# SDR_wt_Schema.net
KiCad netlist of a schematic drawn in Altium Designer
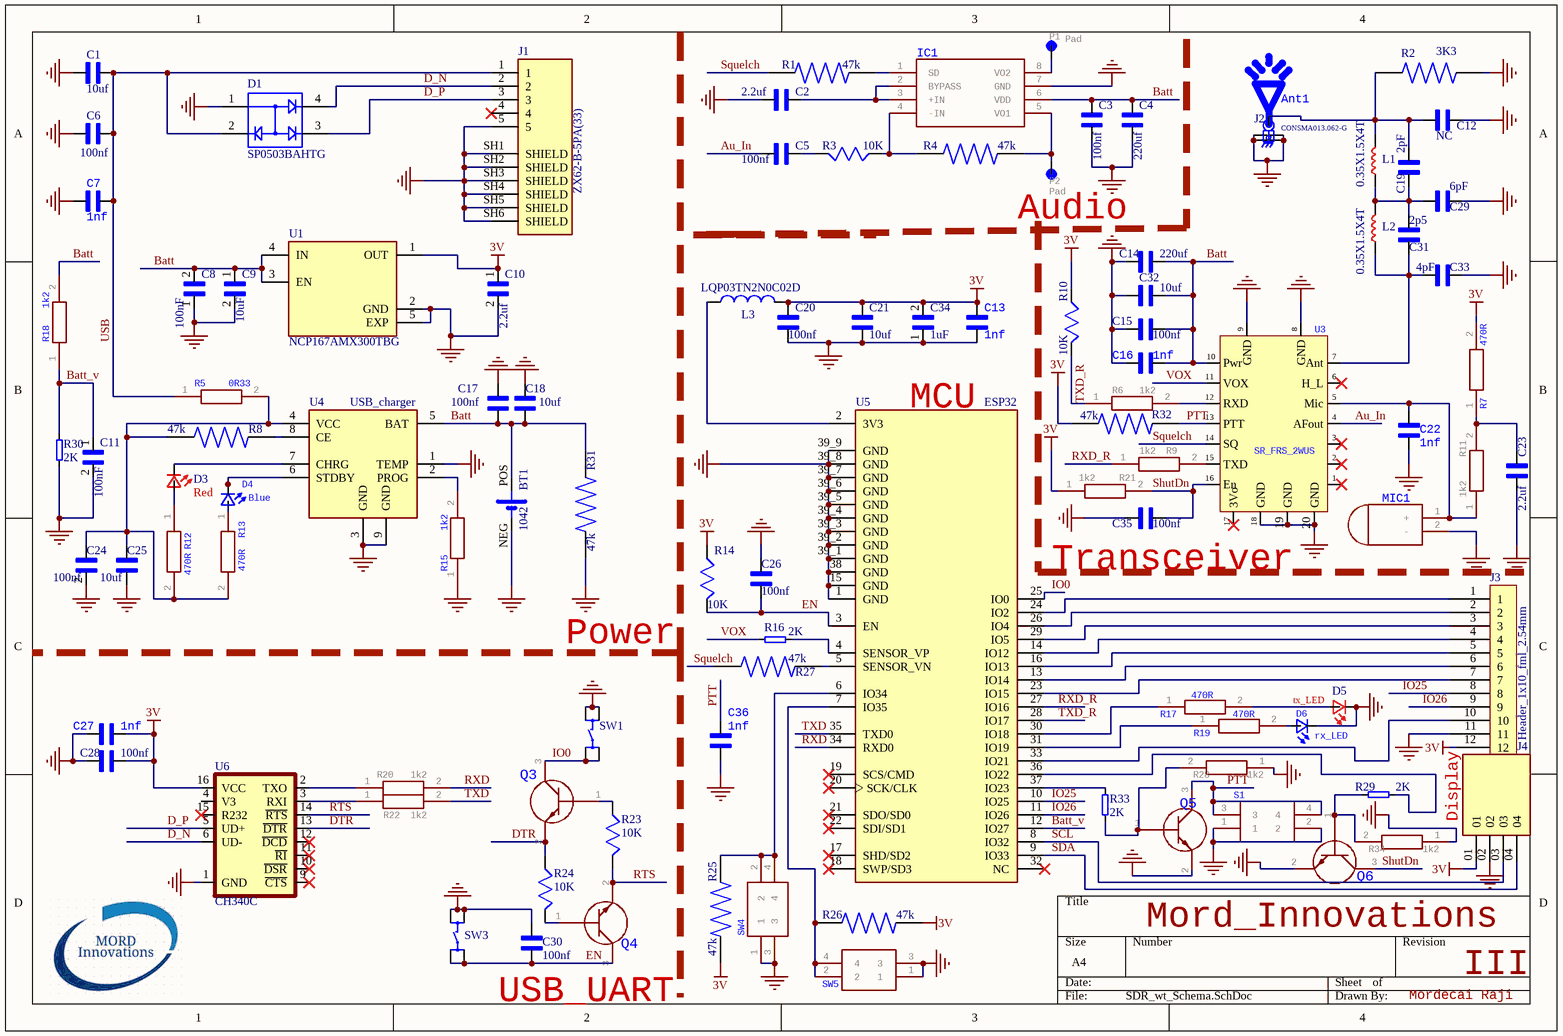
[diagram p0: SDR_wt_Schema.SchDoc]

(export (version "E")
  (design (tool "Eeschema 10.0.6"))
  (components
    (comp (ref "Ant1")
      (value "UHF_Antenna")
      (footprint "Antenna")
      (libsource (lib "SDR_wt_SchLib") (part "Antenna"))
    )
    (comp (ref "BT1")
      (value "1042")
      (footprint "BAT_1042")
      (fields (field (name "MF") "Laird Technologies"))
      (libsource (lib "SDR_wt_SchLib") (part "1042"))
    )
    (comp (ref "C1")
      (value "10uf")
      (footprint "CAPC1608X90N")
      (description "10ÂµF Â±10% 10V Ceramic Capacitor X5R 0603 _1608 Metric_")
      (fields (field (name "MP") "CL10A106KP8NNNC") (field (name "MF") "Samsung"))
      (libsource (lib "") (part "10uf_1"))
    )
    (comp (ref "C2")
      (value "2.2uf")
      (footprint "2u2 cap 0805")
      (description "SMT 0805 ceramic cap X7R 10V 2.2uF")
      (fields (field (name "MP") "GRM21BR71A225KA01L"))
      (libsource (lib "") (part "GRM21BR71A225KA01L_1"))
    )
    (comp (ref "C3")
      (value "100nf")
      (footprint "CAPC1005X55N")
      (description "0.1ÂµF Â±10% 16V Ceramic Capacitor X7R 0402 _1005 Metric_")
      (fields (field (name "MP") "CL05B104KO5NNNC") (field (name "MF") "Samsung Electro-Mechanics"))
      (libsource (lib "") (part "100nf_4"))
    )
    (comp (ref "C4")
      (value "220uf")
      (footprint "220uf_3v3")
      (description "GRM31CR60J227ME11L")
      (fields (field (name "DIGI-KEY_PART_NUMBER") "490-13970-1-ND") (field (name "MF") "Murata Electronics"))
      (libsource (lib "") (part "220uf_6v3_1"))
    )
    (comp (ref "C5")
      (value "100nf")
      (footprint "CAPC1005X55N")
      (description "0.1ÂµF Â±10% 16V Ceramic Capacitor X7R 0402 _1005 Metric_")
      (fields (field (name "MP") "CL05B104KO5NNNC") (field (name "MF") "Samsung Electro-Mechanics"))
      (libsource (lib "") (part "100nf_1"))
    )
    (comp (ref "C6")
      (value "100nf")
      (footprint "CAPC1005X55N")
      (description "0.1ÂµF Â±10% 16V Ceramic Capacitor X7R 0402 _1005 Metric_")
      (fields (field (name "MP") "CL05B104KO5NNNC") (field (name "MF") "Samsung Electro-Mechanics"))
      (libsource (lib "") (part "100nf_1"))
    )
    (comp (ref "C7") (value "1nf") (footprint "1nF CAP") (libsource (lib "") (part "1nF CAP_2")))
    (comp (ref "C8")
      (value "100nF")
      (footprint "CAPC1005X55N")
      (description "0.1ÂµF Â±10% 16V Ceramic Capacitor X7R 0402 _1005 Metric_")
      (fields (field (name "MP") "CL05B104KO5NNNC") (field (name "MF") "Samsung Electro-Mechanics"))
      (libsource (lib "") (part "100nf_2"))
    )
    (comp (ref "C9")
      (value "10uF")
      (footprint "CAPC1608X90N")
      (description "10ÂµF Â±10% 10V Ceramic Capacitor X5R 0603 _1608 Metric_")
      (fields (field (name "MP") "CL10A106KP8NNNC") (field (name "MF") "Samsung"))
      (libsource (lib "") (part "10uf_3"))
    )
    (comp (ref "C10")
      (value "2.2uf")
      (footprint "2u2 cap 0805")
      (description "SMT 0805 ceramic cap X7R 10V 2.2uF")
      (fields (field (name "MP") "GRM21BR71A225KA01L"))
      (libsource (lib "SDR_wt_SchLib") (part "GRM21BR71A225KA01L"))
    )
    (comp (ref "C11")
      (value "100nF")
      (footprint "CAPC1005X55N")
      (description "0.1ÂµF Â±10% 16V Ceramic Capacitor X7R 0402 _1005 Metric_")
      (fields (field (name "MP") "CL05B104KO5NNNC") (field (name "MF") "Samsung Electro-Mechanics"))
      (libsource (lib "SDR_wt_SchLib") (part "100nf"))
    )
    (comp (ref "C12")
      (value "NC")
      (footprint "CAPC1608X90N")
      (description "SMD Capacitor C0G(EIA) with Capacitance: 2.0pF Tol. 0.1pF. Rated Voltage: 100Vdc")
      (fields (field (name "MP") "GCM1885C2A2R0BA16D"))
      (libsource (lib "") (part "GCM1885C2A2R0BA16D_1"))
    )
    (comp (ref "C13") (value "1nf") (footprint "1nF CAP") (libsource (lib "") (part "1nF CAP_1")))
    (comp (ref "C14")
      (value "220uf")
      (footprint "220uf_3v3")
      (description "GRM31CR60J227ME11L")
      (fields (field (name "DIGI-KEY_PART_NUMBER") "490-13970-1-ND") (field (name "MF") "Murata Electronics"))
      (libsource (lib "SDR_wt_SchLib") (part "220uf_6v3"))
    )
    (comp (ref "C15")
      (value "100nf")
      (footprint "CAPC1005X55N")
      (description "0.1ÂµF Â±10% 16V Ceramic Capacitor X7R 0402 _1005 Metric_")
      (fields (field (name "MP") "CL05B104KO5NNNC") (field (name "MF") "Samsung Electro-Mechanics"))
      (libsource (lib "") (part "100nf_1"))
    )
    (comp (ref "C16") (value "1nf") (footprint "1nF CAP") (libsource (lib "SDR_wt_SchLib") (part "1nF CAP")))
    (comp (ref "C17")
      (value "100nf")
      (footprint "CAPC1005X55N")
      (description "0.1ÂµF Â±10% 16V Ceramic Capacitor X7R 0402 _1005 Metric_")
      (fields (field (name "MP") "CL05B104KO5NNNC") (field (name "MF") "Samsung Electro-Mechanics"))
      (libsource (lib "PowerCastle") (part "100nf"))
    )
    (comp (ref "C18")
      (value "10uf")
      (footprint "CAPC1608X90N")
      (description "10ÂµF Â±10% 10V Ceramic Capacitor X5R 0603 _1608 Metric_")
      (fields (field (name "MP") "CL10A106KP8NNNC") (field (name "MF") "Samsung"))
      (libsource (lib "") (part "10uf_2"))
    )
    (comp (ref "C19")
      (value "2pF")
      (footprint "CAPC1608X90N")
      (description "SMD Capacitor C0G(EIA) with Capacitance: 2.0pF Tol. 0.1pF. Rated Voltage: 100Vdc")
      (fields (field (name "MP") "GCM1885C2A2R0BA16D"))
      (libsource (lib "GCM1885C2A2R0BA16D") (part "GCM1885C2A2R0BA16D"))
    )
    (comp (ref "C20")
      (value "100nf")
      (footprint "CAPC1005X55N")
      (description "0.1ÂµF Â±10% 16V Ceramic Capacitor X7R 0402 _1005 Metric_")
      (fields (field (name "MP") "CL05B104KO5NNNC") (field (name "MF") "Samsung Electro-Mechanics"))
      (libsource (lib "PowerCastle") (part "100nf"))
    )
    (comp (ref "C21")
      (value "10uf")
      (footprint "CAPC1608X90N")
      (description "10ÂµF Â±10% 10V Ceramic Capacitor X5R 0603 _1608 Metric_")
      (fields (field (name "MP") "CL10A106KP8NNNC") (field (name "MF") "Samsung"))
      (libsource (lib "") (part "10uf_2"))
    )
    (comp (ref "C22") (value "1nf") (footprint "1nF CAP") (libsource (lib "") (part "1nF CAP_1")))
    (comp (ref "C23")
      (value "2.2uf")
      (footprint "2u2 cap 0805")
      (description "SMT 0805 ceramic cap X7R 10V 2.2uF")
      (fields (field (name "MP") "GRM21BR71A225KA01L"))
      (libsource (lib "") (part "GRM21BR71A225KA01L_2"))
    )
    (comp (ref "C24")
      (value "100nf")
      (footprint "CAPC1005X55N")
      (description "0.1ÂµF Â±10% 16V Ceramic Capacitor X7R 0402 _1005 Metric_")
      (fields (field (name "MP") "CL05B104KO5NNNC") (field (name "MF") "Samsung Electro-Mechanics"))
      (libsource (lib "") (part "100nf_3"))
    )
    (comp (ref "C25")
      (value "10uf")
      (footprint "CAPC1608X90N")
      (description "10ÂµF Â±10% 10V Ceramic Capacitor X5R 0603 _1608 Metric_")
      (fields (field (name "MP") "CL10A106KP8NNNC") (field (name "MF") "Samsung"))
      (libsource (lib "") (part "10uf_2"))
    )
    (comp (ref "C26")
      (value "100nf")
      (footprint "CAPC1005X55N")
      (description "0.1ÂµF Â±10% 16V Ceramic Capacitor X7R 0402 _1005 Metric_")
      (fields (field (name "MP") "CL05B104KO5NNNC") (field (name "MF") "Samsung Electro-Mechanics"))
      (libsource (lib "") (part "100nf_4"))
    )
    (comp (ref "C27") (value "1nf") (footprint "1nF CAP") (libsource (lib "") (part "1nF CAP_2")))
    (comp (ref "C28")
      (value "100nf")
      (footprint "CAPC1005X55N")
      (description "0.1ÂµF Â±10% 16V Ceramic Capacitor X7R 0402 _1005 Metric_")
      (fields (field (name "MP") "CL05B104KO5NNNC") (field (name "MF") "Samsung Electro-Mechanics"))
      (libsource (lib "") (part "100nf_1"))
    )
    (comp (ref "C29")
      (value "6pF")
      (footprint "CAPC1608X90N")
      (description "SMD Capacitor C0G(EIA) with Capacitance: 6.0pF Tol. 0.1pF. Rated Voltage: 100Vdc")
      (fields (field (name "MP") "GCM1885C2A6R0BA16D"))
      (libsource (lib "GCM1885C2A6R0BA16D") (part "GCM1885C2A6R0BA16D"))
    )
    (comp (ref "C30")
      (value "100nf")
      (footprint "CAPC1005X55N")
      (description "0.1ÂµF Â±10% 16V Ceramic Capacitor X7R 0402 _1005 Metric_")
      (fields (field (name "MP") "CL05B104KO5NNNC") (field (name "MF") "Samsung Electro-Mechanics"))
      (libsource (lib "PowerCastle") (part "100nf"))
    )
    (comp (ref "C31")
      (value "2p5")
      (footprint "CAPC1608X90N")
      (description "SMD Capacitor C0G(EIA) with Capacitance: 2.5pF Tol. 0.1pF. Rated Voltage: 100Vdc")
      (fields (field (name "MP") "GCM1885C2A2R5BA16D"))
      (libsource (lib "GCM1885C2A2R5BA16D") (part "GCM1885C2A2R5BA16D"))
    )
    (comp (ref "C32")
      (value "10uf")
      (footprint "CAPC1608X90N")
      (description "10ÂµF Â±10% 10V Ceramic Capacitor X5R 0603 _1608 Metric_")
      (fields (field (name "MP") "CL10A106KP8NNNC") (field (name "MF") "Samsung"))
      (libsource (lib "PowerCastle") (part "10uf"))
    )
    (comp (ref "C33")
      (value "4pF")
      (footprint "CAPC1608X90N")
      (description "SMD Capacitor C0G(EIA) with Capacitance: 4.0pF Tol. 0.1pF. Rated Voltage: 100Vdc")
      (fields (field (name "MP") "GCM1885C2A4R0BA16D"))
      (libsource (lib "SDR_wt_SchLib") (part "GCM1885C2A4R0BA16D"))
    )
    (comp (ref "C34")
      (value "1uF")
      (footprint "CAPC1608X100N")
      (description "1ÂµF Â±10% 10V Ceramic Capacitor X5R 0603 _1608 Metric_")
      (fields (field (name "MF") "Samsung Electro-Mechanics") (field (name "MP") "CL10A105KP8NNNC"))
      (libsource (lib "SDR_wt_SchLib") (part "CL10A105KP8NNNC"))
    )
    (comp (ref "C35")
      (value "100nf")
      (footprint "CAPC1005X55N")
      (description "0.1ÂµF Â±10% 16V Ceramic Capacitor X7R 0402 _1005 Metric_")
      (fields (field (name "MP") "CL05B104KO5NNNC") (field (name "MF") "Samsung Electro-Mechanics"))
      (libsource (lib "") (part "100nf_1"))
    )
    (comp (ref "C36") (value "1nf") (footprint "1nF CAP") (libsource (lib "") (part "1nF CAP_1")))
    (comp (ref "D1")
      (value "SP0503BAHTG")
      (footprint "TVS_SOT143")
      (description "8.5V Clamp Ipp Tvs Diode Surface Mount SOT-143-4")
      (fields (field (name "MF") "Littelfuse Inc.") (field (name "DIGI-KEY_PART_NUMBER") "F2715CT-ND"))
      (libsource (lib "SDR_wt_SchLib") (part "SP0503BAHTG"))
    )
    (comp (ref "D3")
      (value "Red")
      (footprint "0603")
      (description "Red 631nm LED Indication - Discrete 2V 0603 _1608 Metric_")
      (fields (field (name "MF") "Lite-On Inc.") (field (name "DIGI-KEY_PART_NUMBER") "160-1447-1-ND"))
      (libsource (lib "PowerCastle") (part "Red LED"))
    )
    (comp (ref "D4")
      (value "Blue")
      (footprint "19217BHCZL1M2RY3T")
      (fields
        (field (name "MANUFACTURER_PART_NUMBER") "19-217/BHC-ZL1M2RY/3T")
        (field (name "LCSC PART #") "C72041")
      )
      (libsource (lib "PowerCastle") (part "Blue_LED"))
    )
    (comp (ref "D5")
      (value "tx_LED")
      (footprint "0603")
      (description "Red 631nm LED Indication - Discrete 2V 0603 _1608 Metric_")
      (fields (field (name "MF") "Lite-On Inc.") (field (name "DIGI-KEY_PART_NUMBER") "160-1447-1-ND"))
      (libsource (lib "PowerCastle") (part "Red LED"))
    )
    (comp (ref "D6")
      (value "rx_LED")
      (footprint "19217BHCZL1M2RY3T")
      (fields
        (field (name "MANUFACTURER_PART_NUMBER") "19-217/BHC-ZL1M2RY/3T")
        (field (name "LCSC PART #") "C72041")
      )
      (libsource (lib "PowerCastle") (part "Blue_LED"))
    )
    (comp (ref "IC1")
      (value "ic   Source:  Datasheet")
      (footprint "NS8002")
      (fields (field (name "MANUFACTURER_PART_NUMBER") "LM4871"))
      (libsource (lib "SDR_wt_SchLib") (part "LM4871"))
    )
    (comp (ref "J1")
      (value "ZX62-B-5PA(33)")
      (footprint "HRS_ZX62-B-5PA(33)")
      (description "USB - micro B USB 2.0 Receptacle Connector 5 Position Surface Mount, Right Angle")
      (fields (field (name "MP") "ZX62-B-5PA_33_") (field (name "MF") "Hirose"))
      (libsource (lib "SDR_wt_SchLib") (part "ZX62-B-5PA(33)"))
    )
    (comp (ref "J2")
      (value "CONSMA013.062-G")
      (footprint "LINX_CONSMA013.062-G")
      (description "SMA MALE EDGE MOUNT FOR 0.031\" THICK BOARD")
      (libsource (lib "SDR_wt_SchLib") (part "CONSMA013.062-G"))
    )
    (comp (ref "J3")
      (value "Header_1x10_fml_2.54mm")
      (footprint "Header_1x12_fml_2.54mm")
      (fields
        (field (name "MANUFACTURER PART NUMBER") "61301011821")
        (field (name "MANUFACTURER") "Wurth Electronics")
      )
      (libsource (lib "SDR_wt_SchLib") (part "61301011821"))
    )
    (comp (ref "J4")
      (value "SL-104-TT-11")
      (footprint "SAMTEC_SL-104-TT-11")
      (libsource (lib "SDR_wt_SchLib") (part "SL-104-TT-11"))
    )
    (comp (ref "L1")
      (value "0.35X1.5X4T")
      (footprint "0.35X1.5X4T")
      (libsource (lib "SDR_wt_SchLib") (part "0.35X1.5X4T"))
    )
    (comp (ref "L2")
      (value "0.35X1.5X4T")
      (footprint "0.35X1.5X4T")
      (libsource (lib "SDR_wt_SchLib") (part "0.35X1.5X4T"))
    )
    (comp (ref "L3")
      (value "LQP03TN2N0C02D")
      (footprint "INDC0603X33N")
      (description "FIXED IND 2NH 600MA 150 MOHM SMD")
      (libsource (lib "SDR_wt_SchLib") (part "LQP03TN2N0C02D"))
    )
    (comp (ref "MIC1")
      (value "Through Hole,P=1.4mm Electret Condenser Microphone   Source:  Datasheet")
      (footprint "GMI4015P2C42db")
      (fields (field (name "MANUFACTURER_PART_NUMBER") "GMI4015P-2C-42db"))
      (libsource (lib "SDR_wt_SchLib") (part "GMI4015P-2C-42DB"))
    )
    (comp (ref "P1") (value "Pad") (footprint "pad_spkr") (libsource (lib "SDR_wt_SchLib") (part "spk_pad")))
    (comp (ref "P2") (value "Pad") (footprint "pad_spkr") (libsource (lib "SDR_wt_SchLib") (part "spk_pad")))
    (comp (ref "Q3")
      (value "Bipolar Transistors - BJT NPN TRANSISTOR 1.5A 40V   Source:  Datasheet")
      (footprint "SOT95P240X115-3N")
      (fields
        (field (name "MANUFACTURER_PART_NUMBER") "SS8050-G")
        (field (name "MOUSER_PART_NUMBER") "750-SS8050-G")
      )
      (libsource (lib "SDR_wt_SchLib") (part "SS8050-G"))
    )
    (comp (ref "Q4")
      (value "Bipolar Transistors - BJT NPN TRANSISTOR 1.5A 40V   Source:  Datasheet")
      (footprint "SOT95P240X115-3N")
      (fields
        (field (name "MANUFACTURER_PART_NUMBER") "SS8050-G")
        (field (name "MOUSER_PART_NUMBER") "750-SS8050-G")
      )
      (libsource (lib "SDR_wt_SchLib") (part "SS8050-G"))
    )
    (comp (ref "Q5")
      (value "Bipolar Transistors - BJT NPN TRANSISTOR 1.5A 40V   Source:  Datasheet")
      (footprint "SOT95P240X115-3N")
      (fields
        (field (name "MANUFACTURER_PART_NUMBER") "SS8050-G")
        (field (name "MOUSER_PART_NUMBER") "750-SS8050-G")
      )
      (libsource (lib "SDR_wt_SchLib") (part "SS8050-G"))
    )
    (comp (ref "Q6")
      (value "Bipolar Transistors - BJT NPN TRANSISTOR 1.5A 40V   Source:  Datasheet")
      (footprint "SOT95P240X115-3N")
      (fields
        (field (name "MANUFACTURER_PART_NUMBER") "SS8050-G")
        (field (name "MOUSER_PART_NUMBER") "750-SS8050-G")
      )
      (libsource (lib "SDR_wt_SchLib") (part "SS8050-G"))
    )
    (comp (ref "R1")
      (value "47k")
      (footprint "R0805_47K")
      (description "Fixed Resistor CRGCQ 0805 47K 1%")
      (fields (field (name "MP") "CRGCQ0805F47K"))
      (libsource (lib "SDR_wt_SchLib") (part "CRGCQ0805F47K"))
    )
    (comp (ref "R2")
      (value "3K3")
      (footprint "RESC2012X65N")
      (description "Fixed Resistor CRGCQ 0805 3K3 1%")
      (fields (field (name "MP") "CRGCQ0805F3K3"))
      (libsource (lib "CRGCQ0805F3K3") (part "CRGCQ0805F3K3"))
    )
    (comp (ref "R3")
      (value "10K")
      (footprint "R0805")
      (description "RES SMD 10K OHM 1% 1/8W 0805")
      (fields
        (field (name "MANUFACTURER") "Yageo")
        (field (name "MANUFACTURER PART NUMBER") "RC0805FR-0710KL")
      )
      (libsource (lib "SDR_wt_SchLib") (part "RC0805FR-0710KL"))
    )
    (comp (ref "R4")
      (value "47k")
      (footprint "R0805_47K")
      (description "Fixed Resistor CRGCQ 0805 47K 1%")
      (fields (field (name "MP") "CRGCQ0805F47K"))
      (libsource (lib "SDR_wt_SchLib") (part "CRGCQ0805F47K"))
    )
    (comp (ref "R5")
      (value "0R33")
      (footprint "RESC3126X65N")
      (fields
        (field (name "MANUFACTURER_PART_NUMBER") "1210W2F330LT5E")
        (field (name "LCSC PART #") "C95211")
      )
      (libsource (lib "PowerCastle") (part "0R33"))
    )
    (comp (ref "R6")
      (value "1k2")
      (footprint "RESC1608X55N 1K2")
      (description "0603WAF1201T5E")
      (fields (field (name "LCSC PART #") "C22765"))
      (libsource (lib "SDR_wt_SchLib") (part "1K2"))
    )
    (comp (ref "R7")
      (value "470R")
      (footprint "RESC1005X40N")
      (fields
        (field (name "MANUFACTURER_PART_NUMBER") "0402WGF4700TCE")
        (field (name "LCSC PART #") "C25117")
      )
      (libsource (lib "PowerCastle") (part "470R"))
    )
    (comp (ref "R8")
      (value "47k")
      (footprint "R0805_47K")
      (description "Fixed Resistor CRGCQ 0805 47K 1%")
      (fields (field (name "MP") "CRGCQ0805F47K"))
      (libsource (lib "SDR_wt_SchLib") (part "CRGCQ0805F47K"))
    )
    (comp (ref "R9")
      (value "1k2")
      (footprint "RESC1608X55N 1K2")
      (description "0603WAF1201T5E")
      (fields (field (name "LCSC PART #") "C22765"))
      (libsource (lib "SDR_wt_SchLib") (part "1K2"))
    )
    (comp (ref "R10")
      (value "10K")
      (footprint "R0805")
      (description "RES SMD 10K OHM 1% 1/8W 0805")
      (fields
        (field (name "MANUFACTURER") "Yageo")
        (field (name "MANUFACTURER PART NUMBER") "RC0805FR-0710KL")
      )
      (libsource (lib "SDR_wt_SchLib") (part "RC0805FR-0710KL"))
    )
    (comp (ref "R11")
      (value "1k2")
      (footprint "RESC1608X55N 1K2")
      (description "0603WAF1201T5E")
      (fields (field (name "LCSC PART #") "C22765"))
      (libsource (lib "SDR_wt_SchLib") (part "1K2"))
    )
    (comp (ref "R12")
      (value "470R")
      (footprint "RESC1005X40N")
      (fields
        (field (name "MANUFACTURER_PART_NUMBER") "0402WGF4700TCE")
        (field (name "LCSC PART #") "C25117")
      )
      (libsource (lib "PowerCastle") (part "470R"))
    )
    (comp (ref "R13")
      (value "470R")
      (footprint "RESC1005X40N")
      (fields
        (field (name "MANUFACTURER_PART_NUMBER") "0402WGF4700TCE")
        (field (name "LCSC PART #") "C25117")
      )
      (libsource (lib "PowerCastle") (part "470R"))
    )
    (comp (ref "R14")
      (value "10K")
      (footprint "R0805")
      (description "RES SMD 10K OHM 1% 1/8W 0805")
      (fields
        (field (name "MANUFACTURER") "Yageo")
        (field (name "MANUFACTURER PART NUMBER") "RC0805FR-0710KL")
      )
      (libsource (lib "SDR_wt_SchLib") (part "RC0805FR-0710KL"))
    )
    (comp (ref "R15")
      (value "1k2")
      (footprint "RESC1608X55N 1K2")
      (description "0603WAF1201T5E")
      (fields (field (name "LCSC PART #") "C22765"))
      (libsource (lib "SDR_wt_SchLib") (part "1K2"))
    )
    (comp (ref "R16")
      (value "2K")
      (footprint "RESC1005X40N")
      (description "AC Series 0402 0.063 W 2 kOhm Â±1% Â±100 ppm/Â°C SMT Thick Film Chip Resistor")
      (fields (field (name "MP") "AC0402FR-072KL") (field (name "LCSC PART #") "C144770"))
      (libsource (lib "SDR_wt_SchLib") (part "2K"))
    )
    (comp (ref "R17")
      (value "470R")
      (footprint "RESC1005X40N")
      (fields
        (field (name "MANUFACTURER_PART_NUMBER") "0402WGF4700TCE")
        (field (name "LCSC PART #") "C25117")
      )
      (libsource (lib "PowerCastle") (part "470R"))
    )
    (comp (ref "R18")
      (value "1k2")
      (footprint "RESC1608X55N 1K2")
      (description "0603WAF1201T5E")
      (fields (field (name "LCSC PART #") "C22765"))
      (libsource (lib "SDR_wt_SchLib") (part "1K2"))
    )
    (comp (ref "R19")
      (value "470R")
      (footprint "RESC1005X40N")
      (fields
        (field (name "MANUFACTURER_PART_NUMBER") "0402WGF4700TCE")
        (field (name "LCSC PART #") "C25117")
      )
      (libsource (lib "PowerCastle") (part "470R"))
    )
    (comp (ref "R20")
      (value "1k2")
      (footprint "RESC1608X55N 1K2")
      (description "0603WAF1201T5E")
      (fields (field (name "LCSC PART #") "C22765"))
      (libsource (lib "SDR_wt_SchLib") (part "1K2"))
    )
    (comp (ref "R21")
      (value "1k2")
      (footprint "RESC1608X55N 1K2")
      (description "0603WAF1201T5E")
      (fields (field (name "LCSC PART #") "C22765"))
      (libsource (lib "SDR_wt_SchLib") (part "1K2"))
    )
    (comp (ref "R22")
      (value "1k2")
      (footprint "RESC1608X55N 1K2")
      (description "0603WAF1201T5E")
      (fields (field (name "LCSC PART #") "C22765"))
      (libsource (lib "SDR_wt_SchLib") (part "1K2"))
    )
    (comp (ref "R23")
      (value "10K")
      (footprint "R0805")
      (description "RES SMD 10K OHM 1% 1/8W 0805")
      (fields
        (field (name "MANUFACTURER") "Yageo")
        (field (name "MANUFACTURER PART NUMBER") "RC0805FR-0710KL")
      )
      (libsource (lib "SDR_wt_SchLib") (part "RC0805FR-0710KL"))
    )
    (comp (ref "R24")
      (value "10K")
      (footprint "R0805")
      (description "RES SMD 10K OHM 1% 1/8W 0805")
      (fields
        (field (name "MANUFACTURER") "Yageo")
        (field (name "MANUFACTURER PART NUMBER") "RC0805FR-0710KL")
      )
      (libsource (lib "SDR_wt_SchLib") (part "RC0805FR-0710KL"))
    )
    (comp (ref "R25")
      (value "47k")
      (footprint "R0805_47K")
      (description "Fixed Resistor CRGCQ 0805 47K 1%")
      (fields (field (name "MP") "CRGCQ0805F47K"))
      (libsource (lib "SDR_wt_SchLib") (part "CRGCQ0805F47K"))
    )
    (comp (ref "R26")
      (value "47k")
      (footprint "R0805_47K")
      (description "Fixed Resistor CRGCQ 0805 47K 1%")
      (fields (field (name "MP") "CRGCQ0805F47K"))
      (libsource (lib "SDR_wt_SchLib") (part "CRGCQ0805F47K"))
    )
    (comp (ref "R27")
      (value "47k")
      (footprint "R0805_47K")
      (description "Fixed Resistor CRGCQ 0805 47K 1%")
      (fields (field (name "MP") "CRGCQ0805F47K"))
      (libsource (lib "SDR_wt_SchLib") (part "CRGCQ0805F47K"))
    )
    (comp (ref "R28")
      (value "1k2")
      (footprint "RESC1608X55N 1K2")
      (description "0603WAF1201T5E")
      (fields (field (name "LCSC PART #") "C22765"))
      (libsource (lib "SDR_wt_SchLib") (part "1K2"))
    )
    (comp (ref "R29")
      (value "2K")
      (footprint "RESC1005X40N")
      (description "AC Series 0402 0.063 W 2 kOhm Â±1% Â±100 ppm/Â°C SMT Thick Film Chip Resistor")
      (fields (field (name "MP") "AC0402FR-072KL") (field (name "LCSC PART #") "C144770"))
      (libsource (lib "SDR_wt_SchLib") (part "2K"))
    )
    (comp (ref "R30")
      (value "2K")
      (footprint "RESC1005X40N")
      (description "AC Series 0402 0.063 W 2 kOhm Â±1% Â±100 ppm/Â°C SMT Thick Film Chip Resistor")
      (fields (field (name "MP") "AC0402FR-072KL") (field (name "LCSC PART #") "C144770"))
      (libsource (lib "SDR_wt_SchLib") (part "2K"))
    )
    (comp (ref "R31")
      (value "47k")
      (footprint "R0805_47K")
      (description "Fixed Resistor CRGCQ 0805 47K 1%")
      (fields (field (name "MP") "CRGCQ0805F47K"))
      (libsource (lib "SDR_wt_SchLib") (part "CRGCQ0805F47K"))
    )
    (comp (ref "R32")
      (value "47k")
      (footprint "R0805_47K")
      (description "Fixed Resistor CRGCQ 0805 47K 1%")
      (fields (field (name "MP") "CRGCQ0805F47K"))
      (libsource (lib "SDR_wt_SchLib") (part "CRGCQ0805F47K"))
    )
    (comp (ref "R33")
      (value "2K")
      (footprint "RESC1005X40N")
      (description "AC Series 0402 0.063 W 2 kOhm Â±1% Â±100 ppm/Â°C SMT Thick Film Chip Resistor")
      (fields (field (name "MP") "AC0402FR-072KL") (field (name "LCSC PART #") "C144770"))
      (libsource (lib "SDR_wt_SchLib") (part "2K"))
    )
    (comp (ref "R34")
      (value "1k2")
      (footprint "RESC1608X55N 1K2")
      (description "0603WAF1201T5E")
      (fields (field (name "LCSC PART #") "C22765"))
      (libsource (lib "SDR_wt_SchLib") (part "1K2"))
    )
    (comp (ref "S1")
      (value "Black Button Tactile Switch, SPST-NO 50 mA 0.65mm Surface Mount   Source:  Datasheet")
      (footprint "SKSCLAE010")
      (fields
        (field (name "MANUFACTURER_PART_NUMBER") "SKSCLAE010")
        (field (name "MOUSER_PART_NUMBER") "688-SKSCLAE010")
      )
      (libsource (lib "SDR_wt_SchLib") (part "SKSCLAE010"))
    )
    (comp (ref "SW1")
      (value "SKRPABE010")
      (footprint "SKRPABE010")
      (description "Switch Tactile N.O. SPST Button J-Bend 0.05A 16VDC 1.57N SMD Automotive T/R")
      (fields (field (name "MF") "ALPS"))
      (libsource (lib "SDR_wt_SchLib") (part "Tactile_PTT_SKRPABE010"))
    )
    (comp (ref "SW3")
      (value "SKRPABE010")
      (footprint "SKRPABE010")
      (description "Switch Tactile N.O. SPST Button J-Bend 0.05A 16VDC 1.57N SMD Automotive T/R")
      (fields (field (name "MF") "ALPS"))
      (libsource (lib "SDR_wt_SchLib") (part "Tactile_PTT_SKRPABE010"))
    )
    (comp (ref "SW4")
      (value "C & K COMPONENTS - PTS645SM43SMTR92LFS - SWITCH, SPST, 0.05A, 12VDC, SMD, 4.3MM   Source:  Datasheet")
      (footprint "PTS645(SMT)")
      (fields
        (field (name "MANUFACTURER_PART_NUMBER") "PTS645SM43SMTR92LFS")
        (field (name "MOUSER_PART_NUMBER") "611-PTS645SM43SMTR92")
      )
      (libsource (lib "SDR_wt_SchLib") (part "Tactile_PTS645SM43SMTR92LFS"))
    )
    (comp (ref "SW5")
      (value "C & K COMPONENTS - PTS645SM43SMTR92LFS - SWITCH, SPST, 0.05A, 12VDC, SMD, 4.3MM   Source:  Datasheet")
      (footprint "PTS645(SMT)")
      (fields
        (field (name "MANUFACTURER_PART_NUMBER") "PTS645SM43SMTR92LFS")
        (field (name "MOUSER_PART_NUMBER") "611-PTS645SM43SMTR92")
      )
      (libsource (lib "SDR_wt_SchLib") (part "Tactile_PTS645SM43SMTR92LFS"))
    )
    (comp (ref "U1")
      (value "NCP167AMX300TBG")
      (footprint "REG_NCP167BMX330TBG")
      (description "Linear Voltage Regulator IC 1 Output 700mA 4-XDFN _1x1_")
      (fields
        (field (name "DIGI-KEY_PART_NUMBER") "NCP167BMX300TBGOSCT-ND")
        (field (name "MF") "ON Semiconductor")
      )
      (libsource (lib "SDR_wt_SchLib") (part "NCP167BMX330TBG"))
    )
    (comp (ref "U3")
      (value "SR_FRS_2WUS")
      (footprint "SR_FRS_2WUS")
      (libsource (lib "SDR_wt_SchLib") (part "SR_FRS_2WUS"))
    )
    (comp (ref "U4")
      (value "USB_charger")
      (footprint "TP4056")
      (description "Complete single cell Li-Ion battery with a constant current / constant voltage linear charger")
      (fields (field (name "MP") "TP4056") (field (name "MF") "NanJing Top Power ASIC Corp."))
      (libsource (lib "SDR_wt_SchLib") (part "TP4056"))
    )
    (comp (ref "U5")
      (value "ESP32")
      (footprint "ESP32 foot")
      (description "SMD MODULE, ESP32-WROOM-32, ESP32-D0WDQ6")
      (fields
        (field (name "MANUFACTURER") "Espressif Systems")
        (field (name "MANUFACTURER PART NUMBER") "ESP32-WROOM-32")
      )
      (libsource (lib "SDR_wt_SchLib") (part "ESP32-WROOM-32"))
    )
    (comp (ref "U6")
      (value "CH340C")
      (footprint "SO016")
      (description "USB to serial chip CH340")
      (fields (field (name "MF") "WCH"))
      (libsource (lib "SDR_wt_SchLib") (part "CH340C"))
    )
  )
  (nets
    (net (code "1") (name "/Au_In") (class "Default")
      (node (ref "C5") (pin "2") (pinfunction "2_2") (pintype "passive"))
      (node (ref "U3") (pin "4") (pinfunction "AFout_4") (pintype "passive"))
    )
    (net (code "2") (name "/Batt") (class "Default")
      (node (ref "BT1") (pin "POS") (pinfunction "POS_POS") (pintype "passive"))
      (node (ref "C14") (pin "1") (pinfunction "1_1") (pintype "passive"))
      (node (ref "C15") (pin "1") (pinfunction "1_1") (pintype "passive"))
      (node (ref "C16") (pin "1") (pinfunction "1_1") (pintype "passive"))
      (node (ref "C17") (pin "2") (pinfunction "2_2") (pintype "passive"))
      (node (ref "C18") (pin "2") (pinfunction "2_2") (pintype "passive"))
      (node (ref "C3") (pin "2") (pinfunction "2_2") (pintype "passive"))
      (node (ref "C32") (pin "2") (pinfunction "2_2") (pintype "passive"))
      (node (ref "C4") (pin "2") (pinfunction "2_2") (pintype "passive"))
      (node (ref "C8") (pin "2") (pinfunction "2_2") (pintype "passive"))
      (node (ref "C9") (pin "1") (pinfunction "1_1") (pintype "passive"))
      (node (ref "IC1") (pin "6") (pinfunction "VDD_6") (pintype "passive"))
      (node (ref "R18") (pin "2") (pinfunction "2_2") (pintype "passive"))
      (node (ref "R31") (pin "2") (pinfunction "2_2") (pintype "passive"))
      (node (ref "U1") (pin "3") (pinfunction "EN_3") (pintype "passive"))
      (node (ref "U1") (pin "4") (pinfunction "IN_4") (pintype "passive"))
      (node (ref "U3") (pin "10") (pinfunction "Pwr_10") (pintype "passive"))
      (node (ref "U4") (pin "5") (pinfunction "BAT_5") (pintype "passive"))
    )
    (net (code "3") (name "/Batt_v") (class "Default")
      (node (ref "C11") (pin "1") (pinfunction "1_1") (pintype "passive"))
      (node (ref "R18") (pin "1") (pinfunction "1_1") (pintype "passive"))
      (node (ref "R30") (pin "2") (pinfunction "2_2") (pintype "passive"))
      (node (ref "U5") (pin "12") (pinfunction "IO27_12") (pintype "passive"))
    )
    (net (code "4") (name "/DTR") (class "Default")
      (node (ref "Q3") (pin "2") (pinfunction "E_2") (pintype "passive"))
      (node (ref "R24") (pin "1") (pinfunction "1_1") (pintype "passive"))
      (node (ref "U6") (pin "13") (pinfunction "~{DTR}_13") (pintype "passive"))
    )
    (net (code "5") (name "/D_N") (class "Default")
      (node (ref "D1") (pin "4") (pinfunction "4_4") (pintype "passive"))
      (node (ref "J1") (pin "2") (pinfunction "2_2") (pintype "passive"))
      (node (ref "U6") (pin "6") (pinfunction "UD-_6") (pintype "passive"))
    )
    (net (code "6") (name "/D_P") (class "Default")
      (node (ref "D1") (pin "3") (pinfunction "3_3") (pintype "passive"))
      (node (ref "J1") (pin "3") (pinfunction "3_3") (pintype "passive"))
      (node (ref "U6") (pin "5") (pinfunction "UD+_5") (pintype "passive"))
    )
    (net (code "7") (name "/EN") (class "Default")
      (node (ref "C26") (pin "1") (pinfunction "1_1") (pintype "passive"))
      (node (ref "C30") (pin "2") (pinfunction "2_2") (pintype "passive"))
      (node (ref "Q4") (pin "3") (pinfunction "C_3") (pintype "passive"))
      (node (ref "R14") (pin "2") (pinfunction "2_2") (pintype "passive"))
      (node (ref "SW3") (pin "P$1") (pinfunction "P$1_P$1") (pintype "passive"))
      (node (ref "SW3") (pin "P$2") (pinfunction "P$2_P$2") (pintype "passive"))
      (node (ref "U5") (pin "3") (pinfunction "EN_3") (pintype "passive"))
    )
    (net (code "8") (name "/IO0") (class "Default")
      (node (ref "Q3") (pin "3") (pinfunction "C_3") (pintype "passive"))
      (node (ref "SW1") (pin "P$1") (pinfunction "P$1_P$1") (pintype "passive"))
      (node (ref "SW1") (pin "P$2") (pinfunction "P$2_P$2") (pintype "passive"))
      (node (ref "U5") (pin "25") (pinfunction "IO0_25") (pintype "passive"))
    )
    (net (code "9") (name "/IO25") (class "Default")
      (node (ref "J3") (pin "8") (pinfunction "8_8") (pintype "passive"))
      (node (ref "U5") (pin "10") (pinfunction "IO25_10") (pintype "passive"))
    )
    (net (code "10") (name "/IO26") (class "Default")
      (node (ref "J3") (pin "9") (pinfunction "9_9") (pintype "passive"))
      (node (ref "U5") (pin "11") (pinfunction "IO26_11") (pintype "passive"))
    )
    (net (code "11") (name "/PTT") (class "Default")
      (node (ref "C36") (pin "1") (pinfunction "1_1") (pintype "passive"))
      (node (ref "Q5") (pin "3") (pinfunction "C_3") (pintype "passive"))
      (node (ref "R32") (pin "2") (pinfunction "2_2") (pintype "passive"))
      (node (ref "S1") (pin "3") (pinfunction "3_3") (pintype "passive"))
      (node (ref "S1") (pin "4") (pinfunction "4_4") (pintype "passive"))
      (node (ref "U3") (pin "13") (pinfunction "PTT_13") (pintype "passive"))
    )
    (net (code "12") (name "/RTS") (class "Default")
      (node (ref "Q4") (pin "2") (pinfunction "E_2") (pintype "passive"))
      (node (ref "R23") (pin "2") (pinfunction "2_2") (pintype "passive"))
      (node (ref "U6") (pin "14") (pinfunction "~{RTS}_14") (pintype "passive"))
    )
    (net (code "13") (name "/RXD") (class "Default")
      (node (ref "R20") (pin "2") (pinfunction "2_2") (pintype "passive"))
      (node (ref "U5") (pin "34") (pinfunction "RXD0_34") (pintype "passive"))
    )
    (net (code "14") (name "/RXD_R") (class "Default")
      (node (ref "R9") (pin "1") (pinfunction "1_1") (pintype "passive"))
      (node (ref "U5") (pin "27") (pinfunction "IO16_27") (pintype "passive"))
    )
    (net (code "15") (name "/SCL") (class "Default")
      (node (ref "J4") (pin "03") (pinfunction "03_03") (pintype "passive"))
      (node (ref "U5") (pin "8") (pinfunction "IO32_8") (pintype "passive"))
    )
    (net (code "16") (name "/SDA") (class "Default")
      (node (ref "J4") (pin "04") (pinfunction "04_04") (pintype "passive"))
      (node (ref "U5") (pin "9") (pinfunction "IO33_9") (pintype "passive"))
    )
    (net (code "17") (name "/ShutDn") (class "Default")
      (node (ref "C35") (pin "1") (pinfunction "1_1") (pintype "passive"))
      (node (ref "Q6") (pin "3") (pinfunction "C_3") (pintype "passive"))
      (node (ref "R21") (pin "2") (pinfunction "2_2") (pintype "passive"))
      (node (ref "U3") (pin "16") (pinfunction "En_16") (pintype "passive"))
    )
    (net (code "18") (name "/Squelch") (class "Default")
      (node (ref "R1") (pin "1") (pinfunction "1_1") (pintype "passive"))
      (node (ref "R27") (pin "1") (pinfunction "1_1") (pintype "passive"))
      (node (ref "U3") (pin "14") (pinfunction "SQ_14") (pintype "passive"))
    )
    (net (code "19") (name "/TXD") (class "Default")
      (node (ref "R22") (pin "2") (pinfunction "2_2") (pintype "passive"))
      (node (ref "U5") (pin "35") (pinfunction "TXD0_35") (pintype "passive"))
    )
    (net (code "20") (name "/TXD_R") (class "Default")
      (node (ref "R10") (pin "2") (pinfunction "2_2") (pintype "passive"))
      (node (ref "R6") (pin "1") (pinfunction "1_1") (pintype "passive"))
      (node (ref "U5") (pin "28") (pinfunction "IO17_28") (pintype "passive"))
    )
    (net (code "21") (name "/USB") (class "Default")
      (node (ref "C1") (pin "1") (pinfunction "1_1") (pintype "passive"))
      (node (ref "C6") (pin "1") (pinfunction "1_1") (pintype "passive"))
      (node (ref "C7") (pin "2") (pinfunction "2_2") (pintype "passive"))
      (node (ref "D1") (pin "2") (pinfunction "2_2") (pintype "passive"))
      (node (ref "J1") (pin "1") (pinfunction "1_1") (pintype "passive"))
      (node (ref "R5") (pin "1") (pinfunction "1_1") (pintype "passive"))
    )
    (net (code "22") (name "/VOX") (class "Default")
      (node (ref "R16") (pin "1") (pinfunction "1_1") (pintype "passive"))
      (node (ref "U3") (pin "11") (pinfunction "VOX_11") (pintype "passive"))
    )
    (net (code "23") (name "3V") (class "Default")
      (node (ref "C10") (pin "1") (pinfunction "1_1") (pintype "passive"))
      (node (ref "C13") (pin "1") (pinfunction "1_1") (pintype "passive"))
      (node (ref "C20") (pin "1") (pinfunction "1_1") (pintype "passive"))
      (node (ref "C21") (pin "1") (pinfunction "1_1") (pintype "passive"))
      (node (ref "C27") (pin "2") (pinfunction "2_2") (pintype "passive"))
      (node (ref "C28") (pin "1") (pinfunction "1_1") (pintype "passive"))
      (node (ref "C34") (pin "2") (pinfunction "2_2") (pintype "passive"))
      (node (ref "J3") (pin "12") (pinfunction "12_12") (pintype "passive"))
      (node (ref "J4") (pin "01") (pinfunction "01_01") (pintype "passive"))
      (node (ref "L3") (pin "2") (pinfunction "2_2") (pintype "passive"))
      (node (ref "R10") (pin "1") (pinfunction "1_1") (pintype "passive"))
      (node (ref "R14") (pin "1") (pinfunction "1_1") (pintype "passive"))
      (node (ref "R21") (pin "1") (pinfunction "1_1") (pintype "passive"))
      (node (ref "R25") (pin "2") (pinfunction "2_2") (pintype "passive"))
      (node (ref "R26") (pin "2") (pinfunction "2_2") (pintype "passive"))
      (node (ref "R32") (pin "1") (pinfunction "1_1") (pintype "passive"))
      (node (ref "R7") (pin "2") (pinfunction "2_2") (pintype "passive"))
      (node (ref "U1") (pin "1") (pinfunction "OUT_1") (pintype "passive"))
      (node (ref "U6") (pin "16") (pinfunction "VCC_16") (pintype "passive"))
    )
    (net (code "24") (name "GND") (class "Default")
      (node (ref "BT1") (pin "NEG") (pinfunction "NEG_NEG") (pintype "passive"))
      (node (ref "C1") (pin "2") (pinfunction "2_2") (pintype "passive"))
      (node (ref "C10") (pin "2") (pinfunction "2_2") (pintype "passive"))
      (node (ref "C11") (pin "2") (pinfunction "2_2") (pintype "passive"))
      (node (ref "C12") (pin "2") (pinfunction "2_2") (pintype "passive"))
      (node (ref "C13") (pin "2") (pinfunction "2_2") (pintype "passive"))
      (node (ref "C14") (pin "2") (pinfunction "2_2") (pintype "passive"))
      (node (ref "C15") (pin "2") (pinfunction "2_2") (pintype "passive"))
      (node (ref "C16") (pin "2") (pinfunction "2_2") (pintype "passive"))
      (node (ref "C17") (pin "1") (pinfunction "1_1") (pintype "passive"))
      (node (ref "C18") (pin "1") (pinfunction "1_1") (pintype "passive"))
      (node (ref "C2") (pin "2") (pinfunction "2_2") (pintype "passive"))
      (node (ref "C20") (pin "2") (pinfunction "2_2") (pintype "passive"))
      (node (ref "C21") (pin "2") (pinfunction "2_2") (pintype "passive"))
      (node (ref "C22") (pin "2") (pinfunction "2_2") (pintype "passive"))
      (node (ref "C23") (pin "2") (pinfunction "2_2") (pintype "passive"))
      (node (ref "C24") (pin "2") (pinfunction "2_2") (pintype "passive"))
      (node (ref "C25") (pin "2") (pinfunction "2_2") (pintype "passive"))
      (node (ref "C26") (pin "2") (pinfunction "2_2") (pintype "passive"))
      (node (ref "C27") (pin "1") (pinfunction "1_1") (pintype "passive"))
      (node (ref "C28") (pin "2") (pinfunction "2_2") (pintype "passive"))
      (node (ref "C29") (pin "1") (pinfunction "1_1") (pintype "passive"))
      (node (ref "C3") (pin "1") (pinfunction "1_1") (pintype "passive"))
      (node (ref "C30") (pin "1") (pinfunction "1_1") (pintype "passive"))
      (node (ref "C32") (pin "1") (pinfunction "1_1") (pintype "passive"))
      (node (ref "C33") (pin "2") (pinfunction "2_2") (pintype "passive"))
      (node (ref "C34") (pin "1") (pinfunction "1_1") (pintype "passive"))
      (node (ref "C35") (pin "2") (pinfunction "2_2") (pintype "passive"))
      (node (ref "C36") (pin "2") (pinfunction "2_2") (pintype "passive"))
      (node (ref "C4") (pin "1") (pinfunction "1_1") (pintype "passive"))
      (node (ref "C6") (pin "2") (pinfunction "2_2") (pintype "passive"))
      (node (ref "C7") (pin "1") (pinfunction "1_1") (pintype "passive"))
      (node (ref "C8") (pin "1") (pinfunction "1_1") (pintype "passive"))
      (node (ref "C9") (pin "2") (pinfunction "2_2") (pintype "passive"))
      (node (ref "D1") (pin "1") (pinfunction "1_1") (pintype "passive"))
      (node (ref "D5") (pin "1") (pinfunction "K2_1") (pintype "passive"))
      (node (ref "D6") (pin "1") (pinfunction "K2_1") (pintype "passive"))
      (node (ref "IC1") (pin "7") (pinfunction "GND_7") (pintype "passive"))
      (node (ref "J1") (pin "5") (pinfunction "5_5") (pintype "passive"))
      (node (ref "J1") (pin "SH1") (pinfunction "SHIELD_SH1") (pintype "passive"))
      (node (ref "J1") (pin "SH2") (pinfunction "SHIELD_SH2") (pintype "passive"))
      (node (ref "J1") (pin "SH3") (pinfunction "SHIELD_SH3") (pintype "passive"))
      (node (ref "J1") (pin "SH4") (pinfunction "SHIELD_SH4") (pintype "passive"))
      (node (ref "J1") (pin "SH5") (pinfunction "SHIELD_SH5") (pintype "passive"))
      (node (ref "J1") (pin "SH6") (pinfunction "SHIELD_SH6") (pintype "passive"))
      (node (ref "J2") (pin "S1") (pinfunction "2_S1") (pintype "passive"))
      (node (ref "J2") (pin "S2") (pinfunction "2_S2") (pintype "passive"))
      (node (ref "J2") (pin "S3") (pinfunction "2_S3") (pintype "passive"))
      (node (ref "J2") (pin "S4") (pinfunction "2_S4") (pintype "passive"))
      (node (ref "J3") (pin "11") (pinfunction "11_11") (pintype "passive"))
      (node (ref "J4") (pin "02") (pinfunction "02_02") (pintype "passive"))
      (node (ref "MIC1") (pin "2") (pinfunction "-_2") (pintype "passive"))
      (node (ref "Q5") (pin "2") (pinfunction "E_2") (pintype "passive"))
      (node (ref "Q6") (pin "2") (pinfunction "E_2") (pintype "passive"))
      (node (ref "R15") (pin "1") (pinfunction "1_1") (pintype "passive"))
      (node (ref "R2") (pin "2") (pinfunction "2_2") (pintype "passive"))
      (node (ref "R28") (pin "1") (pinfunction "1_1") (pintype "passive"))
      (node (ref "R30") (pin "1") (pinfunction "1_1") (pintype "passive"))
      (node (ref "R31") (pin "1") (pinfunction "1_1") (pintype "passive"))
      (node (ref "R34") (pin "1") (pinfunction "1_1") (pintype "passive"))
      (node (ref "S1") (pin "1") (pinfunction "1_1") (pintype "passive"))
      (node (ref "S1") (pin "2") (pinfunction "2_2") (pintype "passive"))
      (node (ref "SW1") (pin "P$3") (pinfunction "P$3_P$3") (pintype "passive"))
      (node (ref "SW1") (pin "P$4") (pinfunction "P$4_P$4") (pintype "passive"))
      (node (ref "SW3") (pin "P$3") (pinfunction "P$3_P$3") (pintype "passive"))
      (node (ref "SW3") (pin "P$4") (pinfunction "P$4_P$4") (pintype "passive"))
      (node (ref "SW4") (pin "1") (pinfunction "1_1") (pintype "passive"))
      (node (ref "SW4") (pin "3") (pinfunction "3_3") (pintype "passive"))
      (node (ref "SW5") (pin "1") (pinfunction "1_1") (pintype "passive"))
      (node (ref "SW5") (pin "3") (pinfunction "3_3") (pintype "passive"))
      (node (ref "U1") (pin "2") (pinfunction "GND_2") (pintype "power_in"))
      (node (ref "U1") (pin "5") (pinfunction "EXP_5") (pintype "power_in"))
      (node (ref "U3") (pin "18") (pinfunction "GND_18") (pintype "passive"))
      (node (ref "U3") (pin "19") (pinfunction "GND_19") (pintype "passive"))
      (node (ref "U3") (pin "20") (pinfunction "GND_20") (pintype "passive"))
      (node (ref "U3") (pin "8") (pinfunction "GND_8") (pintype "passive"))
      (node (ref "U3") (pin "9") (pinfunction "GND_9") (pintype "passive"))
      (node (ref "U4") (pin "1") (pinfunction "TEMP_1") (pintype "passive"))
      (node (ref "U4") (pin "3") (pinfunction "GND_3") (pintype "passive"))
      (node (ref "U4") (pin "9") (pinfunction "GND_9") (pintype "passive"))
      (node (ref "U5") (pin "1") (pinfunction "GND_1") (pintype "power_in"))
      (node (ref "U5") (pin "15") (pinfunction "GND_15") (pintype "power_in"))
      (node (ref "U5") (pin "38") (pinfunction "GND_38") (pintype "power_in"))
      (node (ref "U5") (pin "39_1") (pinfunction "GND_39_1") (pintype "power_in"))
      (node (ref "U5") (pin "39_2") (pinfunction "GND_39_2") (pintype "power_in"))
      (node (ref "U5") (pin "39_3") (pinfunction "GND_39_3") (pintype "power_in"))
      (node (ref "U5") (pin "39_4") (pinfunction "GND_39_4") (pintype "power_in"))
      (node (ref "U5") (pin "39_5") (pinfunction "GND_39_5") (pintype "power_in"))
      (node (ref "U5") (pin "39_6") (pinfunction "GND_39_6") (pintype "power_in"))
      (node (ref "U5") (pin "39_7") (pinfunction "GND_39_7") (pintype "power_in"))
      (node (ref "U5") (pin "39_8") (pinfunction "GND_39_8") (pintype "power_in"))
      (node (ref "U5") (pin "39_9") (pinfunction "GND_39_9") (pintype "power_in"))
      (node (ref "U6") (pin "1") (pinfunction "GND_1") (pintype "passive"))
    )
    (net (code "25") (name "Net-(C5-Pad1)") (class "Default")
      (node (ref "C5") (pin "1") (pinfunction "1_1") (pintype "passive"))
      (node (ref "R3") (pin "2") (pinfunction "2_2") (pintype "passive"))
    )
    (net (code "26") (name "Net-(C12-Pad1)") (class "Default")
      (node (ref "C12") (pin "1") (pinfunction "1_1") (pintype "passive"))
      (node (ref "C19") (pin "2") (pinfunction "2_2") (pintype "passive"))
      (node (ref "J2") (pin "1") (pinfunction "1_1") (pintype "passive"))
      (node (ref "L1") (pin "2") (pinfunction "2_2") (pintype "passive"))
      (node (ref "R2") (pin "1") (pinfunction "1_1") (pintype "passive"))
    )
    (net (code "27") (name "Net-(C19-Pad1)") (class "Default")
      (node (ref "C19") (pin "1") (pinfunction "1_1") (pintype "passive"))
      (node (ref "C29") (pin "2") (pinfunction "2_2") (pintype "passive"))
      (node (ref "C31") (pin "2") (pinfunction "2_2") (pintype "passive"))
      (node (ref "L1") (pin "1") (pinfunction "1_1") (pintype "passive"))
      (node (ref "L2") (pin "2") (pinfunction "2_2") (pintype "passive"))
    )
    (net (code "28") (name "Net-(C23-Pad1)") (class "Default")
      (node (ref "C23") (pin "1") (pinfunction "1_1") (pintype "passive"))
      (node (ref "R11") (pin "2") (pinfunction "2_2") (pintype "passive"))
      (node (ref "R7") (pin "1") (pinfunction "1_1") (pintype "passive"))
    )
    (net (code "29") (name "Net-(D3-A2)") (class "Default")
      (node (ref "D3") (pin "2") (pinfunction "A2_2") (pintype "passive"))
      (node (ref "R12") (pin "1") (pinfunction "1_1") (pintype "passive"))
    )
    (net (code "30") (name "Net-(D3-K2)") (class "Default")
      (node (ref "D3") (pin "1") (pinfunction "K2_1") (pintype "passive"))
      (node (ref "U4") (pin "7") (pinfunction "CHRG_7") (pintype "passive"))
    )
    (net (code "31") (name "Net-(D4-A2)") (class "Default")
      (node (ref "D4") (pin "2") (pinfunction "A2_2") (pintype "passive"))
      (node (ref "R13") (pin "1") (pinfunction "1_1") (pintype "passive"))
    )
    (net (code "32") (name "Net-(D4-K2)") (class "Default")
      (node (ref "D4") (pin "1") (pinfunction "K2_1") (pintype "passive"))
      (node (ref "U4") (pin "6") (pinfunction "STDBY_6") (pintype "passive"))
    )
    (net (code "33") (name "Net-(D5-A2)") (class "Default")
      (node (ref "D5") (pin "2") (pinfunction "A2_2") (pintype "passive"))
      (node (ref "R17") (pin "2") (pinfunction "2_2") (pintype "passive"))
    )
    (net (code "34") (name "Net-(D6-A2)") (class "Default")
      (node (ref "D6") (pin "2") (pinfunction "A2_2") (pintype "passive"))
      (node (ref "R19") (pin "2") (pinfunction "2_2") (pintype "passive"))
    )
    (net (code "35") (name "Net-(IC1-+IN)") (class "Default")
      (node (ref "C2") (pin "1") (pinfunction "1_1") (pintype "passive"))
      (node (ref "IC1") (pin "2") (pinfunction "BYPASS_2") (pintype "passive"))
      (node (ref "IC1") (pin "3") (pinfunction "+IN_3") (pintype "passive"))
    )
    (net (code "36") (name "Net-(IC1--IN)") (class "Default")
      (node (ref "IC1") (pin "4") (pinfunction "-IN_4") (pintype "passive"))
      (node (ref "R3") (pin "1") (pinfunction "1_1") (pintype "passive"))
      (node (ref "R4") (pin "1") (pinfunction "1_1") (pintype "passive"))
    )
    (net (code "37") (name "Net-(IC1-SD)") (class "Default")
      (node (ref "IC1") (pin "1") (pinfunction "SD_1") (pintype "passive"))
      (node (ref "R1") (pin "2") (pinfunction "2_2") (pintype "passive"))
    )
    (net (code "38") (name "Net-(IC1-VO1)") (class "Default")
      (node (ref "IC1") (pin "5") (pinfunction "VO1_5") (pintype "passive"))
      (node (ref "P2") (pin "1") (pinfunction "1_1") (pintype "passive"))
      (node (ref "R4") (pin "2") (pinfunction "2_2") (pintype "passive"))
    )
    (net (code "39") (name "Net-(IC1-VO2)") (class "Default")
      (node (ref "IC1") (pin "8") (pinfunction "VO2_8") (pintype "passive"))
      (node (ref "P1") (pin "1") (pinfunction "1_1") (pintype "passive"))
    )
    (net (code "40") (name "Net-(MIC1-+)") (class "Default")
      (node (ref "C22") (pin "1") (pinfunction "1_1") (pintype "passive"))
      (node (ref "MIC1") (pin "1") (pinfunction "+_1") (pintype "passive"))
      (node (ref "R11") (pin "1") (pinfunction "1_1") (pintype "passive"))
      (node (ref "U3") (pin "5") (pinfunction "Mic_5") (pintype "passive"))
    )
    (net (code "41") (name "Net-(Q3-B)") (class "Default")
      (node (ref "Q3") (pin "1") (pinfunction "B_1") (pintype "passive"))
      (node (ref "R23") (pin "1") (pinfunction "1_1") (pintype "passive"))
    )
    (net (code "42") (name "Net-(Q4-B)") (class "Default")
      (node (ref "Q4") (pin "1") (pinfunction "B_1") (pintype "passive"))
      (node (ref "R24") (pin "2") (pinfunction "2_2") (pintype "passive"))
    )
    (net (code "43") (name "Net-(Q5-B)") (class "Default")
      (node (ref "Q5") (pin "1") (pinfunction "B_1") (pintype "passive"))
      (node (ref "R28") (pin "2") (pinfunction "2_2") (pintype "passive"))
      (node (ref "R33") (pin "1") (pinfunction "1_1") (pintype "passive"))
    )
    (net (code "44") (name "Net-(Q6-B)") (class "Default")
      (node (ref "Q6") (pin "1") (pinfunction "B_1") (pintype "passive"))
      (node (ref "R29") (pin "2") (pinfunction "2_2") (pintype "passive"))
      (node (ref "R34") (pin "2") (pinfunction "2_2") (pintype "passive"))
    )
    (net (code "45") (name "Net-(U3-Ant)") (class "Default")
      (node (ref "C31") (pin "1") (pinfunction "1_1") (pintype "passive"))
      (node (ref "C33") (pin "1") (pinfunction "1_1") (pintype "passive"))
      (node (ref "L2") (pin "1") (pinfunction "1_1") (pintype "passive"))
      (node (ref "U3") (pin "7") (pinfunction "Ant_7") (pintype "passive"))
    )
    (net (code "46") (name "Net-(U3-RXD)") (class "Default")
      (node (ref "R6") (pin "2") (pinfunction "2_2") (pintype "passive"))
      (node (ref "U3") (pin "12") (pinfunction "RXD_12") (pintype "passive"))
    )
    (net (code "47") (name "Net-(U3-TXD)") (class "Default")
      (node (ref "R9") (pin "2") (pinfunction "2_2") (pintype "passive"))
      (node (ref "U3") (pin "15") (pinfunction "TXD_15") (pintype "passive"))
    )
    (net (code "48") (name "Net-(U4-CE)") (class "Default")
      (node (ref "R8") (pin "2") (pinfunction "2_2") (pintype "passive"))
      (node (ref "U4") (pin "8") (pinfunction "CE_8") (pintype "passive"))
    )
    (net (code "49") (name "Net-(U4-PROG)") (class "Default")
      (node (ref "R15") (pin "2") (pinfunction "2_2") (pintype "passive"))
      (node (ref "U4") (pin "2") (pinfunction "PROG_2") (pintype "passive"))
    )
    (net (code "50") (name "Net-(U4-VCC)") (class "Default")
      (node (ref "C24") (pin "1") (pinfunction "1_1") (pintype "passive"))
      (node (ref "C25") (pin "1") (pinfunction "1_1") (pintype "passive"))
      (node (ref "R12") (pin "2") (pinfunction "2_2") (pintype "passive"))
      (node (ref "R13") (pin "2") (pinfunction "2_2") (pintype "passive"))
      (node (ref "R5") (pin "2") (pinfunction "2_2") (pintype "passive"))
      (node (ref "R8") (pin "1") (pinfunction "1_1") (pintype "passive"))
      (node (ref "U4") (pin "4") (pinfunction "VCC_4") (pintype "passive"))
    )
    (net (code "51") (name "Net-(U5-3V3)") (class "Default")
      (node (ref "L3") (pin "1") (pinfunction "1_1") (pintype "passive"))
      (node (ref "U5") (pin "2") (pinfunction "3V3_2") (pintype "power_in"))
    )
    (net (code "52") (name "Net-(U5-IO2)") (class "Default")
      (node (ref "J3") (pin "1") (pinfunction "1_1") (pintype "passive"))
      (node (ref "U5") (pin "24") (pinfunction "IO2_24") (pintype "passive"))
    )
    (net (code "53") (name "Net-(U5-IO4)") (class "Default")
      (node (ref "J3") (pin "2") (pinfunction "2_2") (pintype "passive"))
      (node (ref "U5") (pin "26") (pinfunction "IO4_26") (pintype "passive"))
    )
    (net (code "54") (name "Net-(U5-IO5)") (class "Default")
      (node (ref "J3") (pin "3") (pinfunction "3_3") (pintype "passive"))
      (node (ref "U5") (pin "29") (pinfunction "IO5_29") (pintype "passive"))
    )
    (net (code "55") (name "Net-(U5-IO12)") (class "Default")
      (node (ref "J3") (pin "4") (pinfunction "4_4") (pintype "passive"))
      (node (ref "U5") (pin "14") (pinfunction "IO12_14") (pintype "passive"))
    )
    (net (code "56") (name "Net-(U5-IO13)") (class "Default")
      (node (ref "J3") (pin "5") (pinfunction "5_5") (pintype "passive"))
      (node (ref "U5") (pin "16") (pinfunction "IO13_16") (pintype "passive"))
    )
    (net (code "57") (name "Net-(U5-IO14)") (class "Default")
      (node (ref "J3") (pin "6") (pinfunction "6_6") (pintype "passive"))
      (node (ref "U5") (pin "13") (pinfunction "IO14_13") (pintype "passive"))
    )
    (net (code "58") (name "Net-(U5-IO15)") (class "Default")
      (node (ref "J3") (pin "7") (pinfunction "7_7") (pintype "passive"))
      (node (ref "U5") (pin "23") (pinfunction "IO15_23") (pintype "passive"))
    )
    (net (code "59") (name "Net-(U5-IO18)") (class "Default")
      (node (ref "R17") (pin "1") (pinfunction "1_1") (pintype "passive"))
      (node (ref "U5") (pin "30") (pinfunction "IO18_30") (pintype "passive"))
    )
    (net (code "60") (name "Net-(U5-IO19)") (class "Default")
      (node (ref "R19") (pin "1") (pinfunction "1_1") (pintype "passive"))
      (node (ref "U5") (pin "31") (pinfunction "IO19_31") (pintype "passive"))
    )
    (net (code "61") (name "Net-(U5-IO21)") (class "Default")
      (node (ref "J3") (pin "10") (pinfunction "10_10") (pintype "passive"))
      (node (ref "U5") (pin "33") (pinfunction "IO21_33") (pintype "passive"))
    )
    (net (code "62") (name "Net-(U5-IO22)") (class "Default")
      (node (ref "R29") (pin "1") (pinfunction "1_1") (pintype "passive"))
      (node (ref "U5") (pin "36") (pinfunction "IO22_36") (pintype "passive"))
    )
    (net (code "63") (name "Net-(U5-IO23)") (class "Default")
      (node (ref "R33") (pin "2") (pinfunction "2_2") (pintype "passive"))
      (node (ref "U5") (pin "37") (pinfunction "IO23_37") (pintype "passive"))
    )
    (net (code "64") (name "Net-(U5-IO34)") (class "Default")
      (node (ref "R25") (pin "1") (pinfunction "1_1") (pintype "passive"))
      (node (ref "SW4") (pin "2") (pinfunction "2_2") (pintype "passive"))
      (node (ref "SW4") (pin "4") (pinfunction "4_4") (pintype "passive"))
      (node (ref "U5") (pin "6") (pinfunction "IO34_6") (pintype "passive"))
    )
    (net (code "65") (name "Net-(U5-IO35)") (class "Default")
      (node (ref "R26") (pin "1") (pinfunction "1_1") (pintype "passive"))
      (node (ref "SW5") (pin "2") (pinfunction "2_2") (pintype "passive"))
      (node (ref "SW5") (pin "4") (pinfunction "4_4") (pintype "passive"))
      (node (ref "U5") (pin "7") (pinfunction "IO35_7") (pintype "passive"))
    )
    (net (code "66") (name "Net-(U5-SENSOR_VN)") (class "Default")
      (node (ref "R27") (pin "2") (pinfunction "2_2") (pintype "passive"))
      (node (ref "U5") (pin "5") (pinfunction "SENSOR_VN_5") (pintype "passive"))
    )
    (net (code "67") (name "Net-(U5-SENSOR_VP)") (class "Default")
      (node (ref "R16") (pin "2") (pinfunction "2_2") (pintype "passive"))
      (node (ref "U5") (pin "4") (pinfunction "SENSOR_VP_4") (pintype "passive"))
    )
    (net (code "68") (name "Net-(U6-RXI)") (class "Default")
      (node (ref "R22") (pin "1") (pinfunction "1_1") (pintype "passive"))
      (node (ref "U6") (pin "3") (pinfunction "RXI_3") (pintype "passive"))
    )
    (net (code "69") (name "Net-(U6-TXO)") (class "Default")
      (node (ref "R20") (pin "1") (pinfunction "1_1") (pintype "passive"))
      (node (ref "U6") (pin "2") (pinfunction "TXO_2") (pintype "passive"))
    )
    (net (code "70") (name "unconnected-(J1-Pad4)") (class "Default")
      (node (ref "J1") (pin "4") (pinfunction "4_4") (pintype "passive+no_connect"))
    )
    (net (code "71") (name "unconnected-(U3-3Vo-Pad17)") (class "Default")
      (node (ref "U3") (pin "17") (pinfunction "3Vo_17") (pintype "passive+no_connect"))
    )
    (net (code "72") (name "unconnected-(U3-19-Pad1)") (class "Default")
      (node (ref "U3") (pin "1") (pinfunction "19_1") (pintype "passive+no_connect"))
    )
    (net (code "73") (name "unconnected-(U3-H_L-Pad6)") (class "Default")
      (node (ref "U3") (pin "6") (pinfunction "H_L_6") (pintype "passive+no_connect"))
    )
    (net (code "74") (name "unconnected-(U3-Pad2)") (class "Default")
      (node (ref "U3") (pin "2") (pinfunction "2_2") (pintype "passive+no_connect"))
    )
    (net (code "75") (name "unconnected-(U3-Pad3)") (class "Default")
      (node (ref "U3") (pin "3") (pinfunction "3_3") (pintype "passive+no_connect"))
    )
    (net (code "76") (name "unconnected-(U5-NC-Pad32)") (class "Default")
      (node (ref "U5") (pin "32") (pinfunction "NC_32") (pintype "passive+no_connect"))
    )
    (net (code "77") (name "unconnected-(U5-SCK{slash}CLK-Pad20)") (class "Default")
      (node (ref "U5") (pin "20") (pinfunction "SCK/CLK_20") (pintype "passive+no_connect"))
    )
    (net (code "78") (name "unconnected-(U5-SCS{slash}CMD-Pad19)") (class "Default")
      (node (ref "U5") (pin "19") (pinfunction "SCS/CMD_19") (pintype "passive+no_connect"))
    )
    (net (code "79") (name "unconnected-(U5-SDI{slash}SD1-Pad22)") (class "Default")
      (node (ref "U5") (pin "22") (pinfunction "SDI/SD1_22") (pintype "passive+no_connect"))
    )
    (net (code "80") (name "unconnected-(U5-SDO{slash}SD0-Pad21)") (class "Default")
      (node (ref "U5") (pin "21") (pinfunction "SDO/SD0_21") (pintype "passive+no_connect"))
    )
    (net (code "81") (name "unconnected-(U5-SHD{slash}SD2-Pad17)") (class "Default")
      (node (ref "U5") (pin "17") (pinfunction "SHD/SD2_17") (pintype "passive+no_connect"))
    )
    (net (code "82") (name "unconnected-(U5-SWP{slash}SD3-Pad18)") (class "Default")
      (node (ref "U5") (pin "18") (pinfunction "SWP/SD3_18") (pintype "passive+no_connect"))
    )
    (net (code "83") (name "unconnected-(U6-R232-Pad15)") (class "Default")
      (node (ref "U6") (pin "15") (pinfunction "R232_15") (pintype "passive+no_connect"))
    )
    (net (code "84") (name "unconnected-(U6-V3-Pad4)") (class "Default")
      (node (ref "U6") (pin "4") (pinfunction "V3_4") (pintype "passive"))
    )
    (net (code "85") (name "unconnected-(U6-~{CTS}-Pad9)") (class "Default")
      (node (ref "U6") (pin "9") (pinfunction "~{CTS}_9") (pintype "passive+no_connect"))
    )
    (net (code "86") (name "unconnected-(U6-~{DCD}-Pad12)") (class "Default")
      (node (ref "U6") (pin "12") (pinfunction "~{DCD}_12") (pintype "passive+no_connect"))
    )
    (net (code "87") (name "unconnected-(U6-~{DSR}-Pad10)") (class "Default")
      (node (ref "U6") (pin "10") (pinfunction "~{DSR}_10") (pintype "passive+no_connect"))
    )
    (net (code "88") (name "unconnected-(U6-~{RI}-Pad11)") (class "Default")
      (node (ref "U6") (pin "11") (pinfunction "~{RI}_11") (pintype "passive+no_connect"))
    )
  )
)
